# bhi260ap.net
KiCad netlist of a schematic drawn in Altium Designer
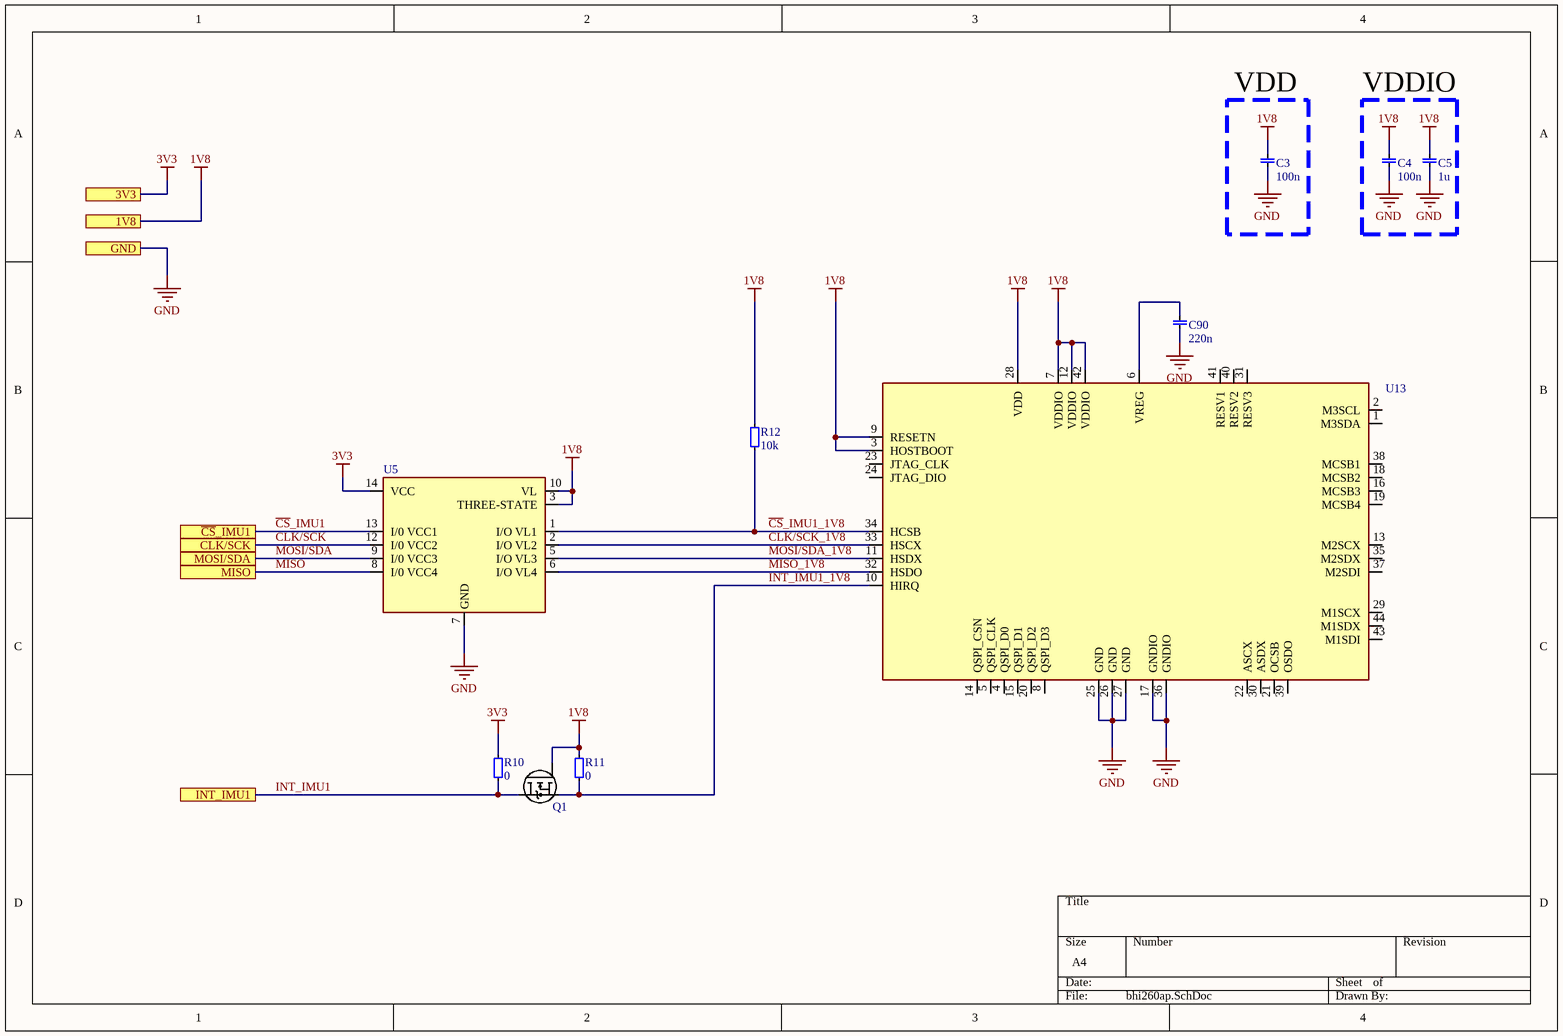
[diagram p0: bhi260ap.SchDoc]

(export (version "E")
  (design (tool "Eeschema 10.0.6"))
  (components
    (comp (ref "C3")
      (value "100n")
      (footprint "0402 CAP")
      (fields (field (name "Comment") "0402 capacitor"))
      (libsource (lib "jclib") (part "0402 capacitor"))
    )
    (comp (ref "C4")
      (value "100n")
      (footprint "0402 CAP")
      (fields (field (name "Comment") "0402 capacitor"))
      (libsource (lib "jclib") (part "0402 capacitor"))
    )
    (comp (ref "C5")
      (value "1u")
      (footprint "0402 CAP")
      (fields (field (name "Comment") "0402 capacitor"))
      (libsource (lib "jclib") (part "0402 capacitor"))
    )
    (comp (ref "C90")
      (value "220n")
      (footprint "0402 CAP")
      (fields (field (name "Comment") "0402 capacitor"))
      (libsource (lib "jclib") (part "0402 capacitor"))
    )
    (comp (ref "Q1")
      (value "BSS138")
      (footprint "SOT323")
      (description "N-Channel Logic Level Enhancement Mode Field Effect Transistor")
      (libsource (lib "jclib") (part "BSS138"))
    )
    (comp (ref "R10")
      (value "0")
      (footprint "0402 res")
      (fields (field (name "Comment") "0603, resistor"))
      (libsource (lib "jclib") (part "0603, resistor"))
    )
    (comp (ref "R11")
      (value "0")
      (footprint "0402 res")
      (fields (field (name "Comment") "0603, resistor"))
      (libsource (lib "jclib") (part "0603, resistor"))
    )
    (comp (ref "R12")
      (value "10k")
      (footprint "0402 res")
      (fields (field (name "Comment") "0402, resistor"))
      (libsource (lib "jclib") (part "0402, resistor"))
    )
    (comp (ref "U5")
      (value "MAX3378E")
      (footprint "TDFN14")
      (description "16 Mbps, Dual/Quad\r\nLow-Voltage Level Translators")
      (libsource (lib "jclib") (part "MAX3378E"))
    )
    (comp (ref "U13")
      (value "BHI260AP")
      (footprint "44-LGA")
      (description "Self-learning AI smart sensor with integrated IMU")
      (libsource (lib "jclib") (part "BHI260AP"))
    )
  )
  (nets
    (net (code "1") (name "/CLK{slash}SCK") (class "Default")
      (node (ref "U5") (pin "12") (pinfunction "I/0_VCC2_12") (pintype "passive"))
    )
    (net (code "2") (name "/CLK{slash}SCK_1V8") (class "Default")
      (node (ref "U13") (pin "33") (pinfunction "HSCX_33") (pintype "passive"))
      (node (ref "U5") (pin "2") (pinfunction "I/O_VL2_2") (pintype "passive"))
    )
    (net (code "3") (name "/INT_IMU1") (class "Default")
      (node (ref "Q1") (pin "3") (pinfunction "D_3") (pintype "passive"))
      (node (ref "R10") (pin "1") (pinfunction "1_1") (pintype "passive"))
    )
    (net (code "4") (name "/INT_IMU1_1V8") (class "Default")
      (node (ref "Q1") (pin "2") (pinfunction "S_2") (pintype "passive"))
      (node (ref "R11") (pin "1") (pinfunction "1_1") (pintype "passive"))
      (node (ref "U13") (pin "10") (pinfunction "HIRQ_10") (pintype "passive"))
    )
    (net (code "5") (name "/MISO") (class "Default")
      (node (ref "U5") (pin "8") (pinfunction "I/0_VCC4_8") (pintype "passive"))
    )
    (net (code "6") (name "/MISO_1V8") (class "Default")
      (node (ref "U13") (pin "32") (pinfunction "HSDO_32") (pintype "passive"))
      (node (ref "U5") (pin "6") (pinfunction "I/O_VL4_6") (pintype "passive"))
    )
    (net (code "7") (name "/MOSI{slash}SDA") (class "Default")
      (node (ref "U5") (pin "9") (pinfunction "I/0_VCC3_9") (pintype "passive"))
    )
    (net (code "8") (name "/MOSI{slash}SDA_1V8") (class "Default")
      (node (ref "U13") (pin "11") (pinfunction "HSDX_11") (pintype "passive"))
      (node (ref "U5") (pin "5") (pinfunction "I/O_VL3_5") (pintype "passive"))
    )
    (net (code "9") (name "/~{CS}_IMU1") (class "Default")
      (node (ref "U5") (pin "13") (pinfunction "I/0_VCC1_13") (pintype "passive"))
    )
    (net (code "10") (name "/~{CS}_IMU1_1V8") (class "Default")
      (node (ref "R12") (pin "1") (pinfunction "1_1") (pintype "passive"))
      (node (ref "U13") (pin "34") (pinfunction "HCSB_34") (pintype "passive"))
      (node (ref "U5") (pin "1") (pinfunction "I/O_VL1_1") (pintype "passive"))
    )
    (net (code "11") (name "1V8") (class "Default")
      (node (ref "C3") (pin "1") (pinfunction "1_1") (pintype "passive"))
      (node (ref "C4") (pin "1") (pinfunction "1_1") (pintype "passive"))
      (node (ref "C5") (pin "1") (pinfunction "1_1") (pintype "passive"))
      (node (ref "Q1") (pin "1") (pinfunction "G_1") (pintype "passive"))
      (node (ref "R11") (pin "0") (pinfunction "0_0") (pintype "passive"))
      (node (ref "R12") (pin "0") (pinfunction "0_0") (pintype "passive"))
      (node (ref "U13") (pin "12") (pinfunction "VDDIO_12") (pintype "passive"))
      (node (ref "U13") (pin "28") (pinfunction "VDD_28") (pintype "passive"))
      (node (ref "U13") (pin "3") (pinfunction "HOSTBOOT_3") (pintype "passive"))
      (node (ref "U13") (pin "42") (pinfunction "VDDIO_42") (pintype "passive"))
      (node (ref "U13") (pin "7") (pinfunction "VDDIO_7") (pintype "passive"))
      (node (ref "U13") (pin "9") (pinfunction "RESETN_9") (pintype "passive"))
      (node (ref "U5") (pin "10") (pinfunction "VL_10") (pintype "passive"))
      (node (ref "U5") (pin "3") (pinfunction "THREE-STATE_3") (pintype "passive"))
    )
    (net (code "12") (name "3V3") (class "Default")
      (node (ref "R10") (pin "0") (pinfunction "0_0") (pintype "passive"))
      (node (ref "U5") (pin "14") (pinfunction "VCC_14") (pintype "passive"))
    )
    (net (code "13") (name "GND") (class "Default")
      (node (ref "C3") (pin "0") (pinfunction "0_0") (pintype "passive"))
      (node (ref "C4") (pin "0") (pinfunction "0_0") (pintype "passive"))
      (node (ref "C5") (pin "0") (pinfunction "0_0") (pintype "passive"))
      (node (ref "C90") (pin "0") (pinfunction "0_0") (pintype "passive"))
      (node (ref "U13") (pin "17") (pinfunction "GNDIO_17") (pintype "passive"))
      (node (ref "U13") (pin "25") (pinfunction "GND_25") (pintype "passive"))
      (node (ref "U13") (pin "26") (pinfunction "GND_26") (pintype "passive"))
      (node (ref "U13") (pin "27") (pinfunction "GND_27") (pintype "passive"))
      (node (ref "U13") (pin "36") (pinfunction "GNDIO_36") (pintype "passive"))
      (node (ref "U5") (pin "7") (pinfunction "GND_7") (pintype "passive"))
    )
    (net (code "14") (name "Net-(U13-VREG)") (class "Default")
      (node (ref "C90") (pin "1") (pinfunction "1_1") (pintype "passive"))
      (node (ref "U13") (pin "6") (pinfunction "VREG_6") (pintype "passive"))
    )
    (net (code "15") (name "unconnected-(U13-ASCX-Pad22)") (class "Default")
      (node (ref "U13") (pin "22") (pinfunction "ASCX_22") (pintype "passive"))
    )
    (net (code "16") (name "unconnected-(U13-ASDX-Pad30)") (class "Default")
      (node (ref "U13") (pin "30") (pinfunction "ASDX_30") (pintype "passive"))
    )
    (net (code "17") (name "unconnected-(U13-JTAG_CLK-Pad23)") (class "Default")
      (node (ref "U13") (pin "23") (pinfunction "JTAG_CLK_23") (pintype "passive"))
    )
    (net (code "18") (name "unconnected-(U13-JTAG_DIO-Pad24)") (class "Default")
      (node (ref "U13") (pin "24") (pinfunction "JTAG_DIO_24") (pintype "passive"))
    )
    (net (code "19") (name "unconnected-(U13-M1SCX-Pad29)") (class "Default")
      (node (ref "U13") (pin "29") (pinfunction "M1SCX_29") (pintype "passive"))
    )
    (net (code "20") (name "unconnected-(U13-M1SDI-Pad43)") (class "Default")
      (node (ref "U13") (pin "43") (pinfunction "M1SDI_43") (pintype "passive"))
    )
    (net (code "21") (name "unconnected-(U13-M1SDX-Pad44)") (class "Default")
      (node (ref "U13") (pin "44") (pinfunction "M1SDX_44") (pintype "passive"))
    )
    (net (code "22") (name "unconnected-(U13-M2SCX-Pad13)") (class "Default")
      (node (ref "U13") (pin "13") (pinfunction "M2SCX_13") (pintype "passive"))
    )
    (net (code "23") (name "unconnected-(U13-M2SDI-Pad37)") (class "Default")
      (node (ref "U13") (pin "37") (pinfunction "M2SDI_37") (pintype "passive"))
    )
    (net (code "24") (name "unconnected-(U13-M2SDX-Pad35)") (class "Default")
      (node (ref "U13") (pin "35") (pinfunction "M2SDX_35") (pintype "passive"))
    )
    (net (code "25") (name "unconnected-(U13-M3SCL-Pad2)") (class "Default")
      (node (ref "U13") (pin "2") (pinfunction "M3SCL_2") (pintype "passive"))
    )
    (net (code "26") (name "unconnected-(U13-M3SDA-Pad1)") (class "Default")
      (node (ref "U13") (pin "1") (pinfunction "M3SDA_1") (pintype "passive"))
    )
    (net (code "27") (name "unconnected-(U13-MCSB1-Pad38)") (class "Default")
      (node (ref "U13") (pin "38") (pinfunction "MCSB1_38") (pintype "passive"))
    )
    (net (code "28") (name "unconnected-(U13-MCSB2-Pad18)") (class "Default")
      (node (ref "U13") (pin "18") (pinfunction "MCSB2_18") (pintype "passive"))
    )
    (net (code "29") (name "unconnected-(U13-MCSB3-Pad16)") (class "Default")
      (node (ref "U13") (pin "16") (pinfunction "MCSB3_16") (pintype "passive"))
    )
    (net (code "30") (name "unconnected-(U13-MCSB4-Pad19)") (class "Default")
      (node (ref "U13") (pin "19") (pinfunction "MCSB4_19") (pintype "passive"))
    )
    (net (code "31") (name "unconnected-(U13-OCSB-Pad21)") (class "Default")
      (node (ref "U13") (pin "21") (pinfunction "OCSB_21") (pintype "passive"))
    )
    (net (code "32") (name "unconnected-(U13-OSDO-Pad39)") (class "Default")
      (node (ref "U13") (pin "39") (pinfunction "OSDO_39") (pintype "passive"))
    )
    (net (code "33") (name "unconnected-(U13-QSPI_CLK-Pad5)") (class "Default")
      (node (ref "U13") (pin "5") (pinfunction "QSPI_CLK_5") (pintype "passive"))
    )
    (net (code "34") (name "unconnected-(U13-QSPI_CSN-Pad14)") (class "Default")
      (node (ref "U13") (pin "14") (pinfunction "QSPI_CSN_14") (pintype "passive"))
    )
    (net (code "35") (name "unconnected-(U13-QSPI_D0-Pad4)") (class "Default")
      (node (ref "U13") (pin "4") (pinfunction "QSPI_D0_4") (pintype "passive"))
    )
    (net (code "36") (name "unconnected-(U13-QSPI_D1-Pad15)") (class "Default")
      (node (ref "U13") (pin "15") (pinfunction "QSPI_D1_15") (pintype "passive"))
    )
    (net (code "37") (name "unconnected-(U13-QSPI_D2-Pad20)") (class "Default")
      (node (ref "U13") (pin "20") (pinfunction "QSPI_D2_20") (pintype "passive"))
    )
    (net (code "38") (name "unconnected-(U13-QSPI_D3-Pad8)") (class "Default")
      (node (ref "U13") (pin "8") (pinfunction "QSPI_D3_8") (pintype "passive"))
    )
    (net (code "39") (name "unconnected-(U13-RESV1-Pad41)") (class "Default")
      (node (ref "U13") (pin "41") (pinfunction "RESV1_41") (pintype "passive"))
    )
    (net (code "40") (name "unconnected-(U13-RESV2-Pad40)") (class "Default")
      (node (ref "U13") (pin "40") (pinfunction "RESV2_40") (pintype "passive"))
    )
    (net (code "41") (name "unconnected-(U13-RESV3-Pad31)") (class "Default")
      (node (ref "U13") (pin "31") (pinfunction "RESV3_31") (pintype "passive"))
    )
  )
)
